# DDS_prototype.net
KiCad netlist of a schematic drawn in EAGLE
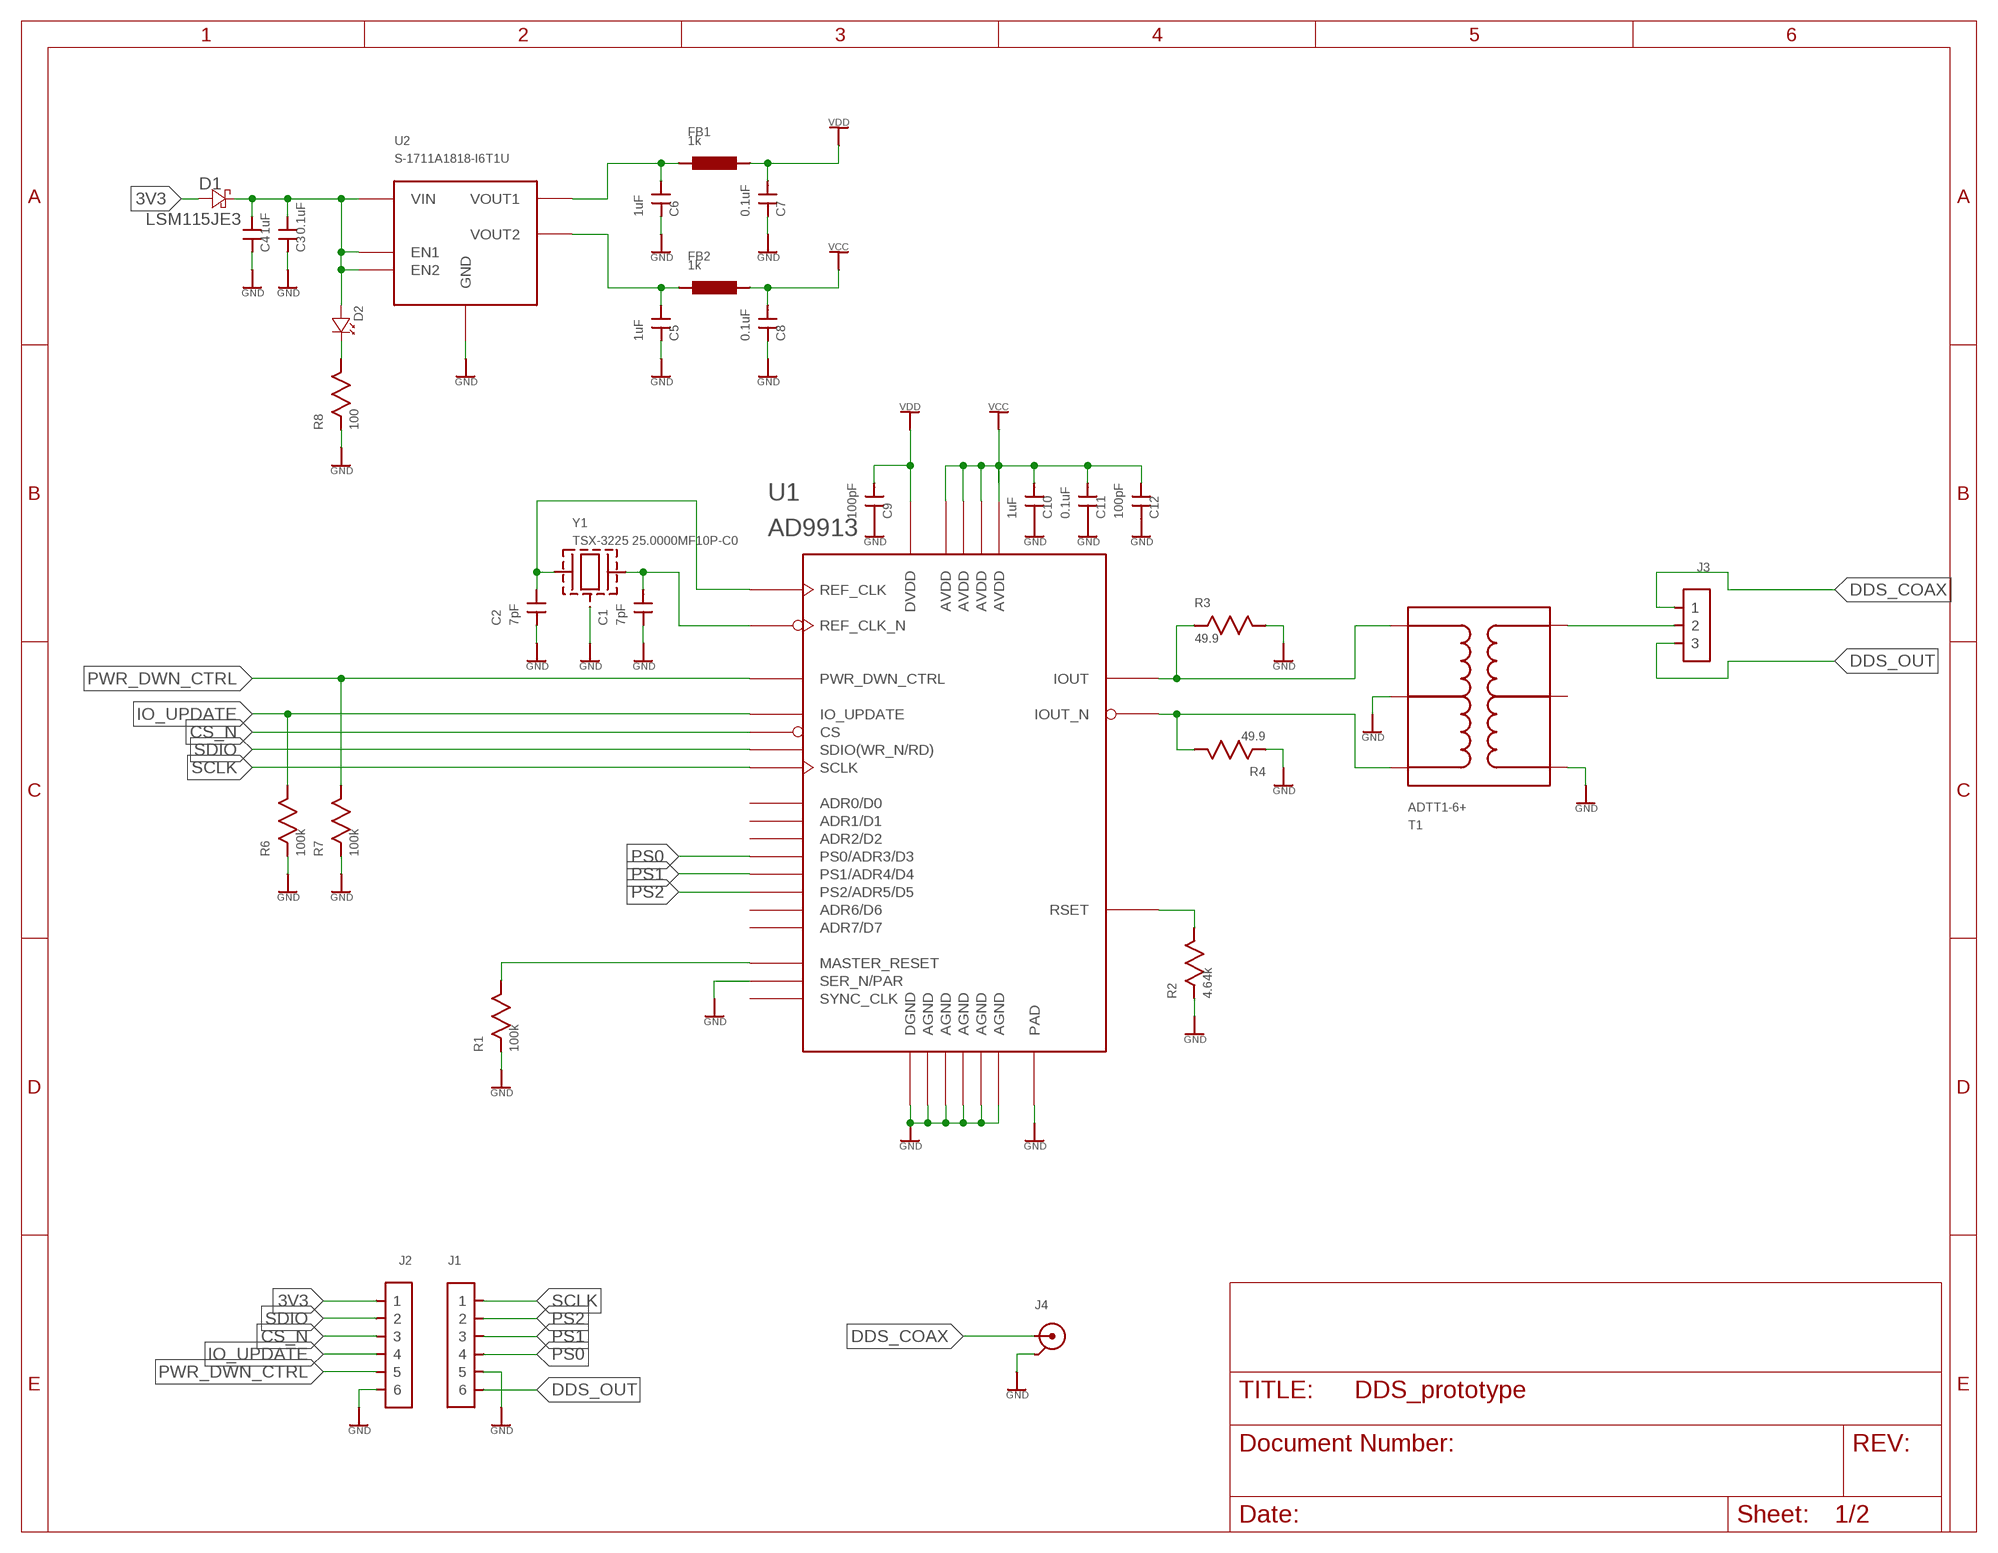
[diagram p0: schematic, sheet 1]

(export (version "E")
  (design (tool "Eeschema 10.0.6"))
  (components
    (comp (ref "C1")
      (value "7pF")
      (footprint "eagle-import:0402")
      (libsource (lib "eagle-import") (part "CC0402DRNPO9BN7R0"))
    )
    (comp (ref "C2")
      (value "7pF")
      (footprint "eagle-import:0402")
      (libsource (lib "eagle-import") (part "CC0402DRNPO9BN7R0"))
    )
    (comp (ref "C3")
      (value "0.1uF")
      (footprint "eagle-import:0402")
      (libsource (lib "eagle-import") (part "CC0402KRX5R7BB104"))
    )
    (comp (ref "C4")
      (value "1uF")
      (footprint "eagle-import:0402")
      (libsource (lib "eagle-import") (part "CC0402KRX5R7BB105"))
    )
    (comp (ref "C5")
      (value "1uF")
      (footprint "eagle-import:0402")
      (libsource (lib "eagle-import") (part "CC0402KRX5R7BB105"))
    )
    (comp (ref "C6")
      (value "1uF")
      (footprint "eagle-import:0402")
      (libsource (lib "eagle-import") (part "CC0402KRX5R7BB105"))
    )
    (comp (ref "C7")
      (value "0.1uF")
      (footprint "eagle-import:0402")
      (libsource (lib "eagle-import") (part "CC0402KRX5R7BB104"))
    )
    (comp (ref "C8")
      (value "0.1uF")
      (footprint "eagle-import:0402")
      (libsource (lib "eagle-import") (part "CC0402KRX5R7BB104"))
    )
    (comp (ref "C9")
      (value "100pF")
      (footprint "eagle-import:0402")
      (libsource (lib "eagle-import") (part "CC0402JRNPO9BN101"))
    )
    (comp (ref "C10")
      (value "1uF")
      (footprint "eagle-import:0402")
      (libsource (lib "eagle-import") (part "CC0402KRX5R7BB105"))
    )
    (comp (ref "C11")
      (value "0.1uF")
      (footprint "eagle-import:0402")
      (libsource (lib "eagle-import") (part "CC0402KRX5R7BB104"))
    )
    (comp (ref "C12")
      (value "100pF")
      (footprint "eagle-import:0402")
      (libsource (lib "eagle-import") (part "CC0402JRNPO9BN101"))
    )
    (comp (ref "D1")
      (value "LSM115JE3")
      (footprint "eagle-import:DO-214BA")
      (libsource (lib "eagle-import") (part "LSM115JE3/TR13"))
    )
    (comp (ref "D2")
      (value "QBLP595-IG")
      (footprint "eagle-import:0402_GREEN")
      (libsource (lib "eagle-import") (part "QBLP595-IG"))
    )
    (comp (ref "FB1")
      (value "1k")
      (footprint "eagle-import:0603")
      (libsource (lib "eagle-import") (part "BLM18KG102SN1D"))
    )
    (comp (ref "FB2")
      (value "1k")
      (footprint "eagle-import:0603")
      (libsource (lib "eagle-import") (part "BLM18KG102SN1D"))
    )
    (comp (ref "J1")
      (value "1X6_MALE_HEADER_0.1")
      (footprint "eagle-import:1X6_MALE_HEADER_0.1")
      (libsource (lib "eagle-import") (part "1X6_MALE_HEADER_0.1"))
    )
    (comp (ref "J2")
      (value "1X6_MALE_HEADER_0.1")
      (footprint "eagle-import:1X6_MALE_HEADER_0.1")
      (libsource (lib "eagle-import") (part "1X6_MALE_HEADER_0.1"))
    )
    (comp (ref "J3")
      (value "1X3_MALE_HEADER_0.1")
      (footprint "eagle-import:1X3_MALE_HEADER_0.1")
      (libsource (lib "eagle-import") (part "1X3_MALE_HEADER_0.1"))
    )
    (comp (ref "J4")
      (value "SMA_EMPCB.SMAFSTJ.B.HT")
      (footprint "eagle-import:EMPCB.SMAFSTJ.B.HT")
      (libsource (lib "eagle-import") (part "SMA_EMPCB.SMAFSTJ.B.HT"))
    )
    (comp (ref "R1")
      (value "100k")
      (footprint "eagle-import:0402")
      (libsource (lib "eagle-import") (part "RC0402JR-07100KL"))
    )
    (comp (ref "R2")
      (value "4.64k")
      (footprint "eagle-import:0402")
      (libsource (lib "eagle-import") (part "RC0402FR-074K64L"))
    )
    (comp (ref "R3")
      (value "49.9")
      (footprint "eagle-import:0402")
      (libsource (lib "eagle-import") (part "RC0402FR-0749R9L"))
    )
    (comp (ref "R4")
      (value "49.9")
      (footprint "eagle-import:0402")
      (libsource (lib "eagle-import") (part "RC0402FR-0749R9L"))
    )
    (comp (ref "R6")
      (value "100k")
      (footprint "eagle-import:0402")
      (libsource (lib "eagle-import") (part "RC0402JR-07100KL"))
    )
    (comp (ref "R7")
      (value "100k")
      (footprint "eagle-import:0402")
      (libsource (lib "eagle-import") (part "RC0402JR-07100KL"))
    )
    (comp (ref "R8")
      (value "100")
      (footprint "eagle-import:0402")
      (libsource (lib "eagle-import") (part "RC0402JR-07100RL"))
    )
    (comp (ref "T1")
      (value "ADTT1-6+")
      (footprint "eagle-import:CD637")
      (libsource (lib "eagle-import") (part "ADTT1-6+"))
    )
    (comp (ref "U1")
      (value "AD9913")
      (footprint "eagle-import:32-LFCSP")
      (libsource (lib "eagle-import") (part "AD9913"))
    )
    (comp (ref "U2")
      (value "S-1711A1818-I6T1U")
      (footprint "eagle-import:SNT-6A")
      (libsource (lib "eagle-import") (part "S-1711"))
    )
    (comp (ref "Y1")
      (value "TSX-3225 25.0000MF10P-C0")
      (footprint "eagle-import:TSX-3225")
      (libsource (lib "eagle-import") (part "TSX-322525.0000MF10P-C0"))
    )
  )
  (nets
    (net (code "1") (name "3V3") (class "Default")
      (node (ref "D1") (pin "A") (pinfunction "A_A") (pintype "passive"))
      (node (ref "J2") (pin "P$1") (pinfunction "1_P$1") (pintype "passive"))
    )
    (net (code "2") (name "CS_N") (class "Default")
      (node (ref "J2") (pin "P$3") (pinfunction "3_P$3") (pintype "passive"))
      (node (ref "U1") (pin "P$28") (pinfunction "CS_P$28") (pintype "bidirectional"))
    )
    (net (code "3") (name "DDS_COAX") (class "Default")
      (node (ref "J3") (pin "P$1") (pinfunction "1_P$1") (pintype "passive"))
      (node (ref "J4") (pin "P$1") (pinfunction "P$1_P$1") (pintype "passive"))
    )
    (net (code "4") (name "DDS_OUT") (class "Default")
      (node (ref "J1") (pin "P$6") (pinfunction "6_P$6") (pintype "passive"))
      (node (ref "J3") (pin "P$3") (pinfunction "3_P$3") (pintype "passive"))
    )
    (net (code "5") (name "GND") (class "Default")
      (node (ref "C1") (pin "1") (pinfunction "P$1_1") (pintype "passive"))
      (node (ref "C10") (pin "1") (pinfunction "P$1_1") (pintype "passive"))
      (node (ref "C11") (pin "1") (pinfunction "P$1_1") (pintype "passive"))
      (node (ref "C12") (pin "1") (pinfunction "P$1_1") (pintype "passive"))
      (node (ref "C2") (pin "1") (pinfunction "P$1_1") (pintype "passive"))
      (node (ref "C3") (pin "1") (pinfunction "P$1_1") (pintype "passive"))
      (node (ref "C4") (pin "1") (pinfunction "P$1_1") (pintype "passive"))
      (node (ref "C5") (pin "1") (pinfunction "P$1_1") (pintype "passive"))
      (node (ref "C6") (pin "1") (pinfunction "P$1_1") (pintype "passive"))
      (node (ref "C7") (pin "1") (pinfunction "P$1_1") (pintype "passive"))
      (node (ref "C8") (pin "1") (pinfunction "P$1_1") (pintype "passive"))
      (node (ref "C9") (pin "1") (pinfunction "P$1_1") (pintype "passive"))
      (node (ref "J1") (pin "P$5") (pinfunction "5_P$5") (pintype "passive"))
      (node (ref "J2") (pin "P$6") (pinfunction "6_P$6") (pintype "passive"))
      (node (ref "J4") (pin "P$2") (pinfunction "P$2_P$2") (pintype "passive"))
      (node (ref "J4") (pin "P$3") (pinfunction "P$2_P$3") (pintype "passive"))
      (node (ref "J4") (pin "P$4") (pinfunction "P$2_P$4") (pintype "passive"))
      (node (ref "J4") (pin "P$5") (pinfunction "P$2_P$5") (pintype "passive"))
      (node (ref "R1") (pin "P$1") (pinfunction "P$1_P$1") (pintype "passive"))
      (node (ref "R2") (pin "P$1") (pinfunction "P$1_P$1") (pintype "passive"))
      (node (ref "R3") (pin "P$2") (pinfunction "P$2_P$2") (pintype "passive"))
      (node (ref "R4") (pin "P$1") (pinfunction "P$1_P$1") (pintype "passive"))
      (node (ref "R6") (pin "P$1") (pinfunction "P$1_P$1") (pintype "passive"))
      (node (ref "R7") (pin "P$1") (pinfunction "P$1_P$1") (pintype "passive"))
      (node (ref "R8") (pin "P$1") (pinfunction "P$1_P$1") (pintype "passive"))
      (node (ref "T1") (pin "P$2") (pinfunction "P$2_P$2") (pintype "passive"))
      (node (ref "T1") (pin "P$6") (pinfunction "P$6_P$6") (pintype "passive"))
      (node (ref "U1") (pin "P$10") (pinfunction "SER_N/PAR_P$10") (pintype "bidirectional"))
      (node (ref "U1") (pin "P$11") (pinfunction "AGND_P$11") (pintype "power_in"))
      (node (ref "U1") (pin "P$15") (pinfunction "AGND_P$15") (pintype "power_in"))
      (node (ref "U1") (pin "P$18") (pinfunction "AGND_P$18") (pintype "power_in"))
      (node (ref "U1") (pin "P$21") (pinfunction "AGND_P$21") (pintype "power_in"))
      (node (ref "U1") (pin "P$23") (pinfunction "AGND_P$23") (pintype "power_in"))
      (node (ref "U1") (pin "P$33") (pinfunction "PAD_P$33") (pintype "power_in"))
      (node (ref "U1") (pin "P$5") (pinfunction "DGND_P$5") (pintype "power_in"))
      (node (ref "U2") (pin "P5") (pinfunction "GND_P5") (pintype "power_in"))
      (node (ref "Y1") (pin "P2") (pinfunction "P$3_P2") (pintype "passive"))
      (node (ref "Y1") (pin "P4") (pinfunction "P$3_P4") (pintype "passive"))
    )
    (net (code "6") (name "IO_UPDATE") (class "Default")
      (node (ref "J2") (pin "P$4") (pinfunction "4_P$4") (pintype "passive"))
      (node (ref "R6") (pin "P$2") (pinfunction "P$2_P$2") (pintype "passive"))
      (node (ref "U1") (pin "P$27") (pinfunction "IO_UPDATE_P$27") (pintype "bidirectional"))
    )
    (net (code "7") (name "Net-(C1-P$2)") (class "Default")
      (node (ref "C1") (pin "2") (pinfunction "P$2_2") (pintype "passive"))
      (node (ref "U1") (pin "P$14") (pinfunction "REF_CLK_N_P$14") (pintype "bidirectional"))
      (node (ref "Y1") (pin "P3") (pinfunction "P$2_P3") (pintype "passive"))
    )
    (net (code "8") (name "Net-(C2-P$2)") (class "Default")
      (node (ref "C2") (pin "2") (pinfunction "P$2_2") (pintype "passive"))
      (node (ref "U1") (pin "P$13") (pinfunction "REF_CLK_P$13") (pintype "bidirectional"))
      (node (ref "Y1") (pin "P1") (pinfunction "P$1_P1") (pintype "passive"))
    )
    (net (code "9") (name "Net-(C3-P$2)") (class "Default")
      (node (ref "C3") (pin "2") (pinfunction "P$2_2") (pintype "passive"))
      (node (ref "C4") (pin "2") (pinfunction "P$2_2") (pintype "passive"))
      (node (ref "D1") (pin "K") (pinfunction "K_K") (pintype "passive"))
      (node (ref "D2") (pin "A") (pinfunction "A_A") (pintype "passive"))
      (node (ref "U2") (pin "P2") (pinfunction "VIN_P2") (pintype "input"))
      (node (ref "U2") (pin "P4") (pinfunction "EN2_P4") (pintype "input"))
      (node (ref "U2") (pin "P6") (pinfunction "EN1_P6") (pintype "input"))
    )
    (net (code "10") (name "Net-(C5-P$2)") (class "Default")
      (node (ref "C5") (pin "2") (pinfunction "P$2_2") (pintype "passive"))
      (node (ref "FB2") (pin "P$1") (pinfunction "P$1_P$1") (pintype "passive"))
      (node (ref "U2") (pin "P3") (pinfunction "VOUT2_P3") (pintype "bidirectional"))
    )
    (net (code "11") (name "Net-(C6-P$2)") (class "Default")
      (node (ref "C6") (pin "2") (pinfunction "P$2_2") (pintype "passive"))
      (node (ref "FB1") (pin "P$1") (pinfunction "P$1_P$1") (pintype "passive"))
      (node (ref "U2") (pin "P1") (pinfunction "VOUT1_P1") (pintype "bidirectional"))
    )
    (net (code "12") (name "Net-(D2-PadK)") (class "Default")
      (node (ref "D2") (pin "K") (pinfunction "K_K") (pintype "passive"))
      (node (ref "R8") (pin "P$2") (pinfunction "P$2_P$2") (pintype "passive"))
    )
    (net (code "13") (name "Net-(J3-2)") (class "Default")
      (node (ref "J3") (pin "P$2") (pinfunction "2_P$2") (pintype "passive"))
      (node (ref "T1") (pin "P$4") (pinfunction "P$4_P$4") (pintype "passive"))
    )
    (net (code "14") (name "Net-(U1-IOUT)") (class "Default")
      (node (ref "R3") (pin "P$1") (pinfunction "P$1_P$1") (pintype "passive"))
      (node (ref "T1") (pin "P$3") (pinfunction "P$3_P$3") (pintype "passive"))
      (node (ref "U1") (pin "P$19") (pinfunction "IOUT_P$19") (pintype "output"))
    )
    (net (code "15") (name "Net-(U1-IOUT_N)") (class "Default")
      (node (ref "R4") (pin "P$2") (pinfunction "P$2_P$2") (pintype "passive"))
      (node (ref "T1") (pin "P$1") (pinfunction "P$1_P$1") (pintype "passive"))
      (node (ref "U1") (pin "P$20") (pinfunction "IOUT_N_P$20") (pintype "output"))
    )
    (net (code "16") (name "Net-(U1-MASTER_RESET)") (class "Default")
      (node (ref "R1") (pin "P$2") (pinfunction "P$2_P$2") (pintype "passive"))
      (node (ref "U1") (pin "P$25") (pinfunction "MASTER_RESET_P$25") (pintype "bidirectional"))
    )
    (net (code "17") (name "Net-(U1-RSET)") (class "Default")
      (node (ref "R2") (pin "P$2") (pinfunction "P$2_P$2") (pintype "passive"))
      (node (ref "U1") (pin "P$24") (pinfunction "RSET_P$24") (pintype "bidirectional"))
    )
    (net (code "18") (name "PS0") (class "Default")
      (node (ref "J1") (pin "P$4") (pinfunction "4_P$4") (pintype "passive"))
      (node (ref "U1") (pin "P$3") (pinfunction "PS0/ADR3/D3_P$3") (pintype "bidirectional"))
    )
    (net (code "19") (name "PS1") (class "Default")
      (node (ref "J1") (pin "P$3") (pinfunction "3_P$3") (pintype "passive"))
      (node (ref "U1") (pin "P$2") (pinfunction "PS1/ADR4/D4_P$2") (pintype "bidirectional"))
    )
    (net (code "20") (name "PS2") (class "Default")
      (node (ref "J1") (pin "P$2") (pinfunction "2_P$2") (pintype "passive"))
      (node (ref "U1") (pin "P$1") (pinfunction "PS2/ADR5/D5_P$1") (pintype "bidirectional"))
    )
    (net (code "21") (name "PWR_DWN_CTRL") (class "Default")
      (node (ref "J2") (pin "P$5") (pinfunction "5_P$5") (pintype "passive"))
      (node (ref "R7") (pin "P$2") (pinfunction "P$2_P$2") (pintype "passive"))
      (node (ref "U1") (pin "P$26") (pinfunction "PWR_DWN_CTRL_P$26") (pintype "bidirectional"))
    )
    (net (code "22") (name "SCLK") (class "Default")
      (node (ref "J1") (pin "P$1") (pinfunction "1_P$1") (pintype "passive"))
      (node (ref "U1") (pin "P$30") (pinfunction "SCLK_P$30") (pintype "bidirectional"))
    )
    (net (code "23") (name "SDIO") (class "Default")
      (node (ref "J2") (pin "P$2") (pinfunction "2_P$2") (pintype "passive"))
      (node (ref "U1") (pin "P$29") (pinfunction "SDIO(WR_N/RD)_P$29") (pintype "bidirectional"))
    )
    (net (code "24") (name "VCC") (class "Default")
      (node (ref "C10") (pin "2") (pinfunction "P$2_2") (pintype "passive"))
      (node (ref "C11") (pin "2") (pinfunction "P$2_2") (pintype "passive"))
      (node (ref "C12") (pin "2") (pinfunction "P$2_2") (pintype "passive"))
      (node (ref "C8") (pin "2") (pinfunction "P$2_2") (pintype "passive"))
      (node (ref "FB2") (pin "P$2") (pinfunction "P$2_P$2") (pintype "passive"))
      (node (ref "U1") (pin "P$12") (pinfunction "AVDD_P$12") (pintype "power_in"))
      (node (ref "U1") (pin "P$16") (pinfunction "AVDD_P$16") (pintype "power_in"))
      (node (ref "U1") (pin "P$17") (pinfunction "AVDD_P$17") (pintype "power_in"))
      (node (ref "U1") (pin "P$22") (pinfunction "AVDD_P$22") (pintype "power_in"))
    )
    (net (code "25") (name "VDD") (class "Default")
      (node (ref "C7") (pin "2") (pinfunction "P$2_2") (pintype "passive"))
      (node (ref "C9") (pin "2") (pinfunction "P$2_2") (pintype "passive"))
      (node (ref "FB1") (pin "P$2") (pinfunction "P$2_P$2") (pintype "passive"))
      (node (ref "U1") (pin "P$4") (pinfunction "DVDD_P$4") (pintype "power_in"))
    )
    (net (code "26") (name "unconnected-(T1-PadP$5)") (class "Default")
      (node (ref "T1") (pin "P$5") (pinfunction "P$5_P$5") (pintype "passive"))
    )
    (net (code "27") (name "unconnected-(U1-ADR0{slash}D0-PadP$8)") (class "Default")
      (node (ref "U1") (pin "P$8") (pinfunction "ADR0/D0_P$8") (pintype "bidirectional"))
    )
    (net (code "28") (name "unconnected-(U1-ADR1{slash}D1-PadP$7)") (class "Default")
      (node (ref "U1") (pin "P$7") (pinfunction "ADR1/D1_P$7") (pintype "bidirectional"))
    )
    (net (code "29") (name "unconnected-(U1-ADR2{slash}D2-PadP$6)") (class "Default")
      (node (ref "U1") (pin "P$6") (pinfunction "ADR2/D2_P$6") (pintype "bidirectional"))
    )
    (net (code "30") (name "unconnected-(U1-ADR6{slash}D6-PadP$32)") (class "Default")
      (node (ref "U1") (pin "P$32") (pinfunction "ADR6/D6_P$32") (pintype "bidirectional"))
    )
    (net (code "31") (name "unconnected-(U1-ADR7{slash}D7-PadP$31)") (class "Default")
      (node (ref "U1") (pin "P$31") (pinfunction "ADR7/D7_P$31") (pintype "bidirectional"))
    )
    (net (code "32") (name "unconnected-(U1-SYNC_CLK-PadP$9)") (class "Default")
      (node (ref "U1") (pin "P$9") (pinfunction "SYNC_CLK_P$9") (pintype "bidirectional"))
    )
  )
)
